# Measurements.net
KiCad netlist of a schematic drawn in Altium Designer
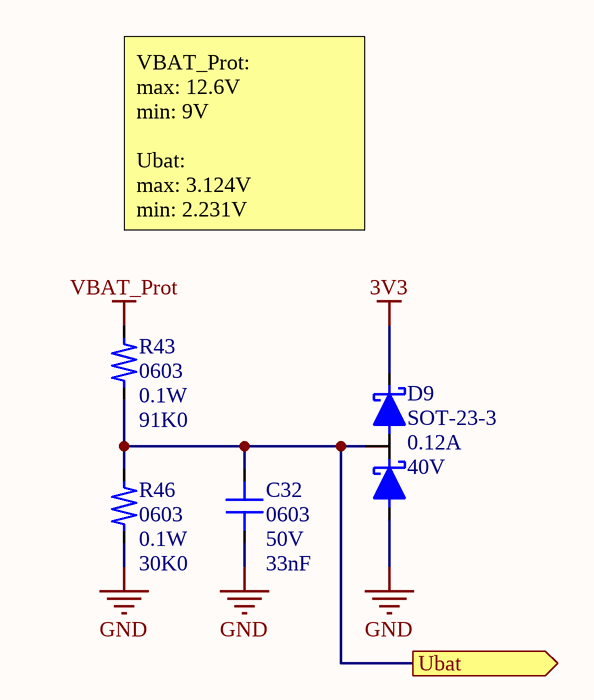
[diagram p0: Measurements.SchDoc]

(export (version "E")
  (design (tool "Eeschema 10.0.6"))
  (components
    (comp (ref "C32")
      (value "0603")
      (footprint "C_0603")
      (fields
        (field (name "TOLERANCE") "10%")
        (field (name "PART NUMBER") "CL10B333KB8NNNC")
        (field (name "RATING") "50V")
        (field (name "ALTIUM_VALUE") "33nF")
        (field (name "NI PART NUMBER") "716045-01")
      )
      (libsource (lib "Components") (part "Capacitor_Chip"))
    )
    (comp (ref "D9")
      (value "SOT-23-3")
      (footprint "SOT-23-3")
      (fields
        (field (name "PART NUMBER") "BAS40-04")
        (field (name "RATING") "0.12A")
        (field (name "ALTIUM_VALUE") "40V")
      )
      (libsource (lib "Components") (part "Diode_Schottky_Series"))
    )
    (comp (ref "R43")
      (value "0603")
      (footprint "R_0603")
      (fields
        (field (name "TOLERANCE") "1%")
        (field (name "PART NUMBER") "CR-03FL7---91K")
        (field (name "RATING") "0.1W")
        (field (name "ALTIUM_VALUE") "91K0")
        (field (name "NI PART NUMBER") "612775-01")
      )
      (libsource (lib "Components") (part "Resistor_Chip"))
    )
    (comp (ref "R46")
      (value "0603")
      (footprint "R_0603")
      (fields
        (field (name "TOLERANCE") "1%")
        (field (name "PART NUMBER") "CR-03FL7---30K")
        (field (name "RATING") "0.1W")
        (field (name "ALTIUM_VALUE") "30K0")
        (field (name "NI PART NUMBER") "612699-01")
      )
      (libsource (lib "Components") (part "Resistor_Chip"))
    )
  )
  (nets
    (net (code "1") (name "/Ubat") (class "Default")
      (node (ref "C32") (pin "2") (pinfunction "C2_2") (pintype "passive"))
      (node (ref "D9") (pin "3") (pinfunction "DCA_3") (pintype "passive"))
      (node (ref "R43") (pin "1") (pinfunction "R1_1") (pintype "passive"))
      (node (ref "R46") (pin "2") (pinfunction "R2_2") (pintype "passive"))
    )
    (net (code "2") (name "3V3") (class "Default")
      (node (ref "D9") (pin "2") (pinfunction "DC_2") (pintype "passive"))
    )
    (net (code "3") (name "GND") (class "Default")
      (node (ref "C32") (pin "1") (pinfunction "C1_1") (pintype "passive"))
      (node (ref "D9") (pin "1") (pinfunction "DA_1") (pintype "passive"))
      (node (ref "R46") (pin "1") (pinfunction "R1_1") (pintype "passive"))
    )
    (net (code "4") (name "VBAT_Prot") (class "Default")
      (node (ref "R43") (pin "2") (pinfunction "R2_2") (pintype "passive"))
    )
  )
)
